# main.net
KiCad netlist of a schematic drawn in EAGLE
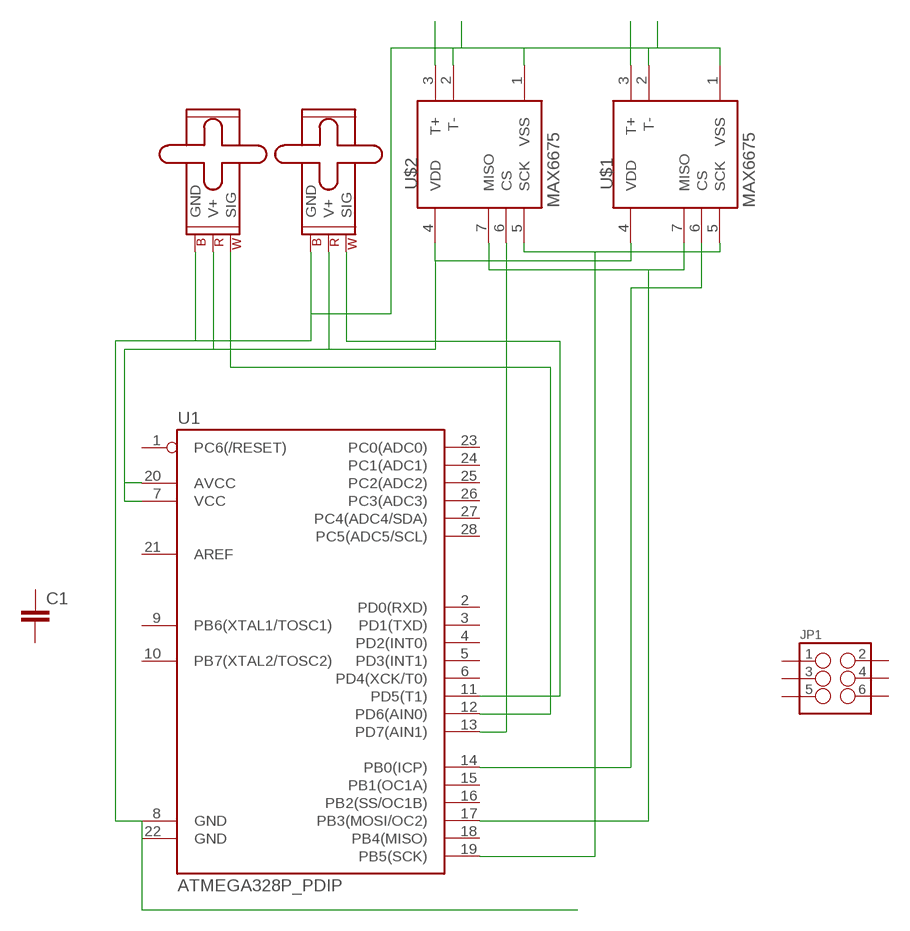
[diagram p0: schematic, sheet 1]

(export (version "E")
  (design (tool "Eeschema 10.0.6"))
  (components
    (comp (ref "C1")
      (value "0.1UF-50V-20%(PTH)KIT-EZ")
      (footprint "eagle-import:CAP-PTH-SMALL-KIT")
      (libsource (lib "eagle-import") (part "0.1UF-50V-20%(PTH)KIT-EZ"))
    )
    (comp (ref "JP1")
      (value "M03X2")
      (footprint "eagle-import:2X3-SHROUDED")
      (libsource (lib "eagle-import") (part "M03X2"))
    )
    (comp (ref "M1")
      (value "SMALL_SERVO")
      (footprint "eagle-import:1X03")
      (libsource (lib "eagle-import") (part "SMALL_SERVO"))
    )
    (comp (ref "M2")
      (value "SMALL_SERVO")
      (footprint "eagle-import:1X03")
      (libsource (lib "eagle-import") (part "SMALL_SERVO"))
    )
    (comp (ref "U$1")
      (value "MAX6675")
      (footprint "eagle-import:SO08-MAX6675")
      (libsource (lib "eagle-import") (part "MAX6675"))
    )
    (comp (ref "U$2")
      (value "MAX6675")
      (footprint "eagle-import:SO08-MAX6675")
      (libsource (lib "eagle-import") (part "MAX6675"))
    )
    (comp (ref "U1")
      (value "ATMEGA328P_PDIP")
      (footprint "eagle-import:DIL28-3")
      (libsource (lib "eagle-import") (part "ATMEGA328P_PDIP"))
    )
  )
  (nets
    (net (code "1") (name "Net-(M1-GND)") (class "Default")
      (node (ref "M1") (pin "3") (pinfunction "GND_3") (pintype "bidirectional"))
      (node (ref "M2") (pin "3") (pinfunction "GND_3") (pintype "bidirectional"))
      (node (ref "U$1") (pin "1") (pinfunction "VSS_1") (pintype "bidirectional"))
      (node (ref "U$1") (pin "2") (pinfunction "T-_2") (pintype "bidirectional"))
      (node (ref "U$2") (pin "1") (pinfunction "VSS_1") (pintype "bidirectional"))
      (node (ref "U$2") (pin "2") (pinfunction "T-_2") (pintype "bidirectional"))
      (node (ref "U1") (pin "22") (pinfunction "GND_22") (pintype "bidirectional"))
      (node (ref "U1") (pin "8") (pinfunction "GND_8") (pintype "bidirectional"))
    )
    (net (code "2") (name "Net-(M1-SIG)") (class "Default")
      (node (ref "M1") (pin "1") (pinfunction "SIG_1") (pintype "bidirectional"))
      (node (ref "U1") (pin "12") (pinfunction "PD6(AIN0)_12") (pintype "bidirectional"))
    )
    (net (code "3") (name "Net-(M1-V+)") (class "Default")
      (node (ref "M1") (pin "2") (pinfunction "V+_2") (pintype "bidirectional"))
      (node (ref "M2") (pin "2") (pinfunction "V+_2") (pintype "bidirectional"))
      (node (ref "U$1") (pin "4") (pinfunction "VDD_4") (pintype "bidirectional"))
      (node (ref "U$2") (pin "4") (pinfunction "VDD_4") (pintype "bidirectional"))
      (node (ref "U1") (pin "20") (pinfunction "AVCC_20") (pintype "bidirectional"))
      (node (ref "U1") (pin "7") (pinfunction "VCC_7") (pintype "bidirectional"))
    )
    (net (code "4") (name "Net-(M2-SIG)") (class "Default")
      (node (ref "M2") (pin "1") (pinfunction "SIG_1") (pintype "bidirectional"))
      (node (ref "U1") (pin "11") (pinfunction "PD5(T1)_11") (pintype "bidirectional"))
    )
    (net (code "5") (name "Net-(U$1-CS)") (class "Default")
      (node (ref "U$1") (pin "6") (pinfunction "CS_6") (pintype "bidirectional"))
      (node (ref "U1") (pin "14") (pinfunction "PB0(ICP)_14") (pintype "bidirectional"))
    )
    (net (code "6") (name "Net-(U$1-MISO)") (class "Default")
      (node (ref "U$1") (pin "7") (pinfunction "MISO_7") (pintype "bidirectional"))
      (node (ref "U$2") (pin "7") (pinfunction "MISO_7") (pintype "bidirectional"))
      (node (ref "U1") (pin "17") (pinfunction "PB3(MOSI/OC2)_17") (pintype "bidirectional"))
    )
    (net (code "7") (name "Net-(U$1-SCK)") (class "Default")
      (node (ref "U$1") (pin "5") (pinfunction "SCK_5") (pintype "bidirectional"))
      (node (ref "U$2") (pin "5") (pinfunction "SCK_5") (pintype "bidirectional"))
      (node (ref "U1") (pin "19") (pinfunction "PB5(SCK)_19") (pintype "bidirectional"))
    )
    (net (code "8") (name "Net-(U$2-CS)") (class "Default")
      (node (ref "U$2") (pin "6") (pinfunction "CS_6") (pintype "bidirectional"))
      (node (ref "U1") (pin "13") (pinfunction "PD7(AIN1)_13") (pintype "bidirectional"))
    )
    (net (code "9") (name "unconnected-(C1-Pad1)") (class "Default")
      (node (ref "C1") (pin "1") (pinfunction "1_1") (pintype "passive"))
    )
    (net (code "10") (name "unconnected-(C1-Pad2)") (class "Default")
      (node (ref "C1") (pin "2") (pinfunction "2_2") (pintype "passive"))
    )
    (net (code "11") (name "unconnected-(JP1-Pad1)") (class "Default")
      (node (ref "JP1") (pin "1") (pinfunction "1_1") (pintype "bidirectional"))
    )
    (net (code "12") (name "unconnected-(JP1-Pad2)") (class "Default")
      (node (ref "JP1") (pin "2") (pinfunction "2_2") (pintype "bidirectional"))
    )
    (net (code "13") (name "unconnected-(JP1-Pad3)") (class "Default")
      (node (ref "JP1") (pin "3") (pinfunction "3_3") (pintype "bidirectional"))
    )
    (net (code "14") (name "unconnected-(JP1-Pad4)") (class "Default")
      (node (ref "JP1") (pin "4") (pinfunction "4_4") (pintype "bidirectional"))
    )
    (net (code "15") (name "unconnected-(JP1-Pad5)") (class "Default")
      (node (ref "JP1") (pin "5") (pinfunction "5_5") (pintype "bidirectional"))
    )
    (net (code "16") (name "unconnected-(JP1-Pad6)") (class "Default")
      (node (ref "JP1") (pin "6") (pinfunction "6_6") (pintype "bidirectional"))
    )
    (net (code "17") (name "unconnected-(U$1-T+-Pad3)") (class "Default")
      (node (ref "U$1") (pin "3") (pinfunction "T+_3") (pintype "bidirectional"))
    )
    (net (code "18") (name "unconnected-(U$2-T+-Pad3)") (class "Default")
      (node (ref "U$2") (pin "3") (pinfunction "T+_3") (pintype "bidirectional"))
    )
    (net (code "19") (name "unconnected-(U1-AREF-Pad21)") (class "Default")
      (node (ref "U1") (pin "21") (pinfunction "AREF_21") (pintype "bidirectional"))
    )
    (net (code "20") (name "unconnected-(U1-PB1(OC1A)-Pad15)") (class "Default")
      (node (ref "U1") (pin "15") (pinfunction "PB1(OC1A)_15") (pintype "bidirectional"))
    )
    (net (code "21") (name "unconnected-(U1-PB2(SS{slash}OC1B)-Pad16)") (class "Default")
      (node (ref "U1") (pin "16") (pinfunction "PB2(SS/OC1B)_16") (pintype "bidirectional"))
    )
    (net (code "22") (name "unconnected-(U1-PB4(MISO)-Pad18)") (class "Default")
      (node (ref "U1") (pin "18") (pinfunction "PB4(MISO)_18") (pintype "bidirectional"))
    )
    (net (code "23") (name "unconnected-(U1-PB6(XTAL1{slash}TOSC1)-Pad9)") (class "Default")
      (node (ref "U1") (pin "9") (pinfunction "PB6(XTAL1/TOSC1)_9") (pintype "bidirectional"))
    )
    (net (code "24") (name "unconnected-(U1-PB7(XTAL2{slash}TOSC2)-Pad10)") (class "Default")
      (node (ref "U1") (pin "10") (pinfunction "PB7(XTAL2/TOSC2)_10") (pintype "bidirectional"))
    )
    (net (code "25") (name "unconnected-(U1-PC0(ADC0)-Pad23)") (class "Default")
      (node (ref "U1") (pin "23") (pinfunction "PC0(ADC0)_23") (pintype "bidirectional"))
    )
    (net (code "26") (name "unconnected-(U1-PC1(ADC1)-Pad24)") (class "Default")
      (node (ref "U1") (pin "24") (pinfunction "PC1(ADC1)_24") (pintype "bidirectional"))
    )
    (net (code "27") (name "unconnected-(U1-PC2(ADC2)-Pad25)") (class "Default")
      (node (ref "U1") (pin "25") (pinfunction "PC2(ADC2)_25") (pintype "bidirectional"))
    )
    (net (code "28") (name "unconnected-(U1-PC3(ADC3)-Pad26)") (class "Default")
      (node (ref "U1") (pin "26") (pinfunction "PC3(ADC3)_26") (pintype "bidirectional"))
    )
    (net (code "29") (name "unconnected-(U1-PC4(ADC4{slash}SDA)-Pad27)") (class "Default")
      (node (ref "U1") (pin "27") (pinfunction "PC4(ADC4/SDA)_27") (pintype "bidirectional"))
    )
    (net (code "30") (name "unconnected-(U1-PC5(ADC5{slash}SCL)-Pad28)") (class "Default")
      (node (ref "U1") (pin "28") (pinfunction "PC5(ADC5/SCL)_28") (pintype "bidirectional"))
    )
    (net (code "31") (name "unconnected-(U1-PC6({slash}RESET)-Pad1)") (class "Default")
      (node (ref "U1") (pin "1") (pinfunction "PC6(/RESET)_1") (pintype "bidirectional"))
    )
    (net (code "32") (name "unconnected-(U1-PD0(RXD)-Pad2)") (class "Default")
      (node (ref "U1") (pin "2") (pinfunction "PD0(RXD)_2") (pintype "bidirectional"))
    )
    (net (code "33") (name "unconnected-(U1-PD1(TXD)-Pad3)") (class "Default")
      (node (ref "U1") (pin "3") (pinfunction "PD1(TXD)_3") (pintype "bidirectional"))
    )
    (net (code "34") (name "unconnected-(U1-PD2(INT0)-Pad4)") (class "Default")
      (node (ref "U1") (pin "4") (pinfunction "PD2(INT0)_4") (pintype "bidirectional"))
    )
    (net (code "35") (name "unconnected-(U1-PD3(INT1)-Pad5)") (class "Default")
      (node (ref "U1") (pin "5") (pinfunction "PD3(INT1)_5") (pintype "bidirectional"))
    )
    (net (code "36") (name "unconnected-(U1-PD4(XCK{slash}T0)-Pad6)") (class "Default")
      (node (ref "U1") (pin "6") (pinfunction "PD4(XCK/T0)_6") (pintype "bidirectional"))
    )
  )
)
